# Extender-PCB.net
KiCad netlist of a schematic drawn in EAGLE
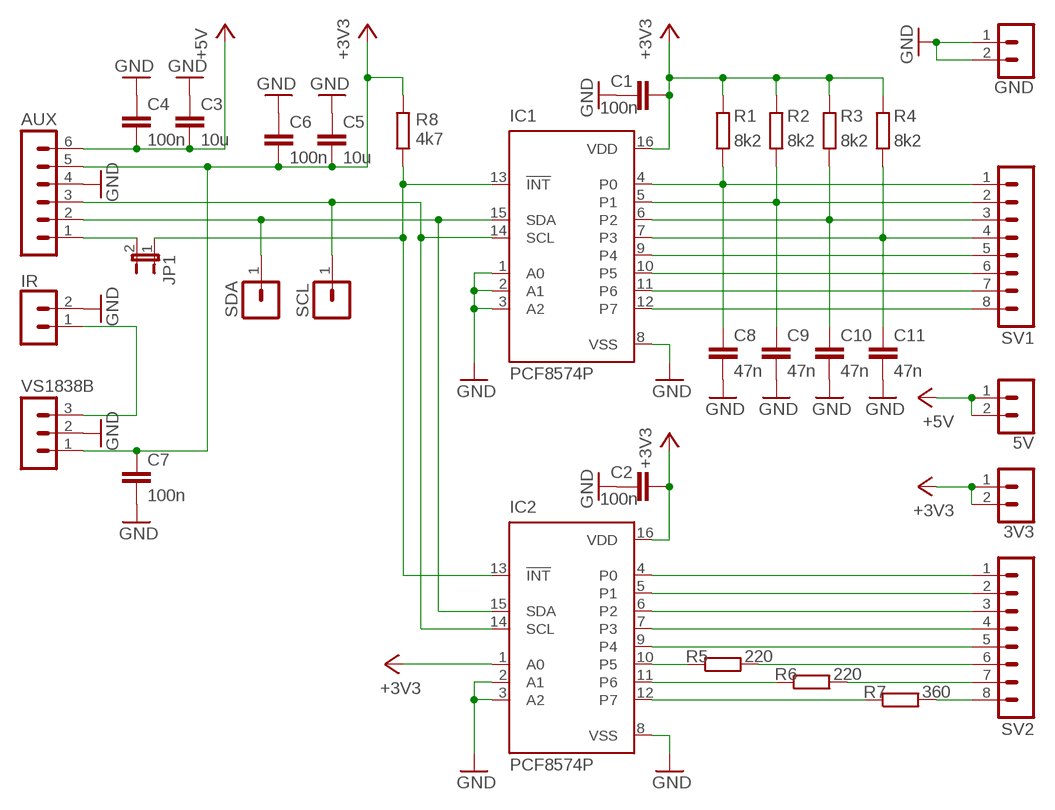
[diagram p0: schematic, sheet 1]

(export (version "E")
  (design (tool "Eeschema 10.0.6"))
  (components
    (comp (ref "3V3")
      (value "MA02-1")
      (footprint "eagle-import:MA02-1")
      (libsource (lib "eagle-import") (part "MA02-1"))
    )
    (comp (ref "5V")
      (value "MA02-1")
      (footprint "eagle-import:MA02-1")
      (libsource (lib "eagle-import") (part "MA02-1"))
    )
    (comp (ref "AUX")
      (value "MA06-1")
      (footprint "eagle-import:MA06-1")
      (libsource (lib "eagle-import") (part "MA06-1"))
    )
    (comp (ref "C1")
      (value "100n")
      (footprint "eagle-import:C1206")
      (libsource (lib "eagle-import") (part "C-EUC1206"))
    )
    (comp (ref "C2")
      (value "100n")
      (footprint "eagle-import:C1206")
      (libsource (lib "eagle-import") (part "C-EUC1206"))
    )
    (comp (ref "C3")
      (value "10u")
      (footprint "eagle-import:C1206")
      (libsource (lib "eagle-import") (part "C-EUC1206"))
    )
    (comp (ref "C4")
      (value "100n")
      (footprint "eagle-import:C1206")
      (libsource (lib "eagle-import") (part "C-EUC1206"))
    )
    (comp (ref "C5")
      (value "10u")
      (footprint "eagle-import:C1206")
      (libsource (lib "eagle-import") (part "C-EUC1206"))
    )
    (comp (ref "C6")
      (value "100n")
      (footprint "eagle-import:C1206")
      (libsource (lib "eagle-import") (part "C-EUC1206"))
    )
    (comp (ref "C7")
      (value "100n")
      (footprint "eagle-import:C1206")
      (libsource (lib "eagle-import") (part "C-EUC1206"))
    )
    (comp (ref "C8")
      (value "47n")
      (footprint "eagle-import:C1206")
      (libsource (lib "eagle-import") (part "C-EUC1206"))
    )
    (comp (ref "C9")
      (value "47n")
      (footprint "eagle-import:C1206")
      (libsource (lib "eagle-import") (part "C-EUC1206"))
    )
    (comp (ref "C10")
      (value "47n")
      (footprint "eagle-import:C1206")
      (libsource (lib "eagle-import") (part "C-EUC1206"))
    )
    (comp (ref "C11")
      (value "47n")
      (footprint "eagle-import:C1206")
      (libsource (lib "eagle-import") (part "C-EUC1206"))
    )
    (comp (ref "GND")
      (value "MA02-1")
      (footprint "eagle-import:MA02-1")
      (libsource (lib "eagle-import") (part "MA02-1"))
    )
    (comp (ref "IC1")
      (value "PCF8574P")
      (footprint "eagle-import:DIL16")
      (fields (field (name "MPN") "PCF8574PN"))
      (libsource (lib "eagle-import") (part "PCF8574P"))
    )
    (comp (ref "IC2")
      (value "PCF8574P")
      (footprint "eagle-import:DIL16")
      (fields (field (name "MPN") "PCF8574PN"))
      (libsource (lib "eagle-import") (part "PCF8574P"))
    )
    (comp (ref "IR")
      (value "MA02-1")
      (footprint "eagle-import:MA02-1")
      (libsource (lib "eagle-import") (part "MA02-1"))
    )
    (comp (ref "JP1")
      (value "JP1E")
      (footprint "eagle-import:JP1")
      (libsource (lib "eagle-import") (part "JP1E"))
    )
    (comp (ref "R1")
      (value "8k2")
      (footprint "eagle-import:R1206")
      (libsource (lib "eagle-import") (part "R-EU_R1206"))
    )
    (comp (ref "R2")
      (value "8k2")
      (footprint "eagle-import:R1206")
      (libsource (lib "eagle-import") (part "R-EU_R1206"))
    )
    (comp (ref "R3")
      (value "8k2")
      (footprint "eagle-import:R1206")
      (libsource (lib "eagle-import") (part "R-EU_R1206"))
    )
    (comp (ref "R4")
      (value "8k2")
      (footprint "eagle-import:R1206")
      (libsource (lib "eagle-import") (part "R-EU_R1206"))
    )
    (comp (ref "R5")
      (value "220")
      (footprint "eagle-import:0207_10")
      (libsource (lib "eagle-import") (part "R-EU_0207/10"))
    )
    (comp (ref "R6")
      (value "220")
      (footprint "eagle-import:0207_10")
      (libsource (lib "eagle-import") (part "R-EU_0207/10"))
    )
    (comp (ref "R7")
      (value "360")
      (footprint "eagle-import:0207_10")
      (libsource (lib "eagle-import") (part "R-EU_0207/10"))
    )
    (comp (ref "R8")
      (value "4k7")
      (footprint "eagle-import:0207_10")
      (libsource (lib "eagle-import") (part "R-EU_0207/10"))
    )
    (comp (ref "SCL")
      (value "MA01-1")
      (footprint "eagle-import:MA01-1")
      (libsource (lib "eagle-import") (part "MA01-1"))
    )
    (comp (ref "SDA")
      (value "MA01-1")
      (footprint "eagle-import:MA01-1")
      (libsource (lib "eagle-import") (part "MA01-1"))
    )
    (comp (ref "SV1")
      (value "MA08-1")
      (footprint "eagle-import:MA08-1")
      (libsource (lib "eagle-import") (part "MA08-1"))
    )
    (comp (ref "SV2")
      (value "MA08-1")
      (footprint "eagle-import:MA08-1")
      (libsource (lib "eagle-import") (part "MA08-1"))
    )
    (comp (ref "VS1838B")
      (value "MA03-1")
      (footprint "eagle-import:MA03-1")
      (libsource (lib "eagle-import") (part "MA03-1"))
    )
  )
  (nets
    (net (code "1") (name "+3V3") (class "Default")
      (node (ref "3V3") (pin "1") (pinfunction "1_1") (pintype "passive"))
      (node (ref "3V3") (pin "2") (pinfunction "2_2") (pintype "passive"))
      (node (ref "AUX") (pin "5") (pinfunction "5_5") (pintype "passive"))
      (node (ref "C1") (pin "2") (pinfunction "2_2") (pintype "passive"))
      (node (ref "C2") (pin "2") (pinfunction "2_2") (pintype "passive"))
      (node (ref "C5") (pin "2") (pinfunction "2_2") (pintype "passive"))
      (node (ref "C6") (pin "2") (pinfunction "2_2") (pintype "passive"))
      (node (ref "C7") (pin "1") (pinfunction "1_1") (pintype "passive"))
      (node (ref "IC1") (pin "16") (pinfunction "VDD_16") (pintype "power_in"))
      (node (ref "IC2") (pin "1") (pinfunction "A0_1") (pintype "input"))
      (node (ref "IC2") (pin "16") (pinfunction "VDD_16") (pintype "power_in"))
      (node (ref "R1") (pin "2") (pinfunction "2_2") (pintype "passive"))
      (node (ref "R2") (pin "2") (pinfunction "2_2") (pintype "passive"))
      (node (ref "R3") (pin "2") (pinfunction "2_2") (pintype "passive"))
      (node (ref "R4") (pin "2") (pinfunction "2_2") (pintype "passive"))
      (node (ref "R8") (pin "2") (pinfunction "2_2") (pintype "passive"))
      (node (ref "VS1838B") (pin "1") (pinfunction "1_1") (pintype "passive"))
    )
    (net (code "2") (name "+5V") (class "Default")
      (node (ref "5V") (pin "1") (pinfunction "1_1") (pintype "passive"))
      (node (ref "5V") (pin "2") (pinfunction "2_2") (pintype "passive"))
      (node (ref "AUX") (pin "6") (pinfunction "6_6") (pintype "passive"))
      (node (ref "C3") (pin "2") (pinfunction "2_2") (pintype "passive"))
      (node (ref "C4") (pin "2") (pinfunction "2_2") (pintype "passive"))
    )
    (net (code "3") (name "GND") (class "Default")
      (node (ref "AUX") (pin "4") (pinfunction "4_4") (pintype "passive"))
      (node (ref "C1") (pin "1") (pinfunction "1_1") (pintype "passive"))
      (node (ref "C10") (pin "2") (pinfunction "2_2") (pintype "passive"))
      (node (ref "C11") (pin "2") (pinfunction "2_2") (pintype "passive"))
      (node (ref "C2") (pin "1") (pinfunction "1_1") (pintype "passive"))
      (node (ref "C3") (pin "1") (pinfunction "1_1") (pintype "passive"))
      (node (ref "C4") (pin "1") (pinfunction "1_1") (pintype "passive"))
      (node (ref "C5") (pin "1") (pinfunction "1_1") (pintype "passive"))
      (node (ref "C6") (pin "1") (pinfunction "1_1") (pintype "passive"))
      (node (ref "C7") (pin "2") (pinfunction "2_2") (pintype "passive"))
      (node (ref "C8") (pin "2") (pinfunction "2_2") (pintype "passive"))
      (node (ref "C9") (pin "2") (pinfunction "2_2") (pintype "passive"))
      (node (ref "GND") (pin "1") (pinfunction "1_1") (pintype "passive"))
      (node (ref "GND") (pin "2") (pinfunction "2_2") (pintype "passive"))
      (node (ref "IC1") (pin "1") (pinfunction "A0_1") (pintype "input"))
      (node (ref "IC1") (pin "2") (pinfunction "A1_2") (pintype "input"))
      (node (ref "IC1") (pin "3") (pinfunction "A2_3") (pintype "input"))
      (node (ref "IC1") (pin "8") (pinfunction "VSS_8") (pintype "power_in"))
      (node (ref "IC2") (pin "2") (pinfunction "A1_2") (pintype "input"))
      (node (ref "IC2") (pin "3") (pinfunction "A2_3") (pintype "input"))
      (node (ref "IC2") (pin "8") (pinfunction "VSS_8") (pintype "power_in"))
      (node (ref "IR") (pin "2") (pinfunction "2_2") (pintype "passive"))
      (node (ref "VS1838B") (pin "2") (pinfunction "2_2") (pintype "passive"))
    )
    (net (code "4") (name "Net-(AUX-Pad1)") (class "Default")
      (node (ref "AUX") (pin "1") (pinfunction "1_1") (pintype "passive"))
      (node (ref "JP1") (pin "2") (pinfunction "2_2") (pintype "passive"))
    )
    (net (code "5") (name "Net-(IC1-P0)") (class "Default")
      (node (ref "C8") (pin "1") (pinfunction "1_1") (pintype "passive"))
      (node (ref "IC1") (pin "4") (pinfunction "P0_4") (pintype "bidirectional"))
      (node (ref "R1") (pin "1") (pinfunction "1_1") (pintype "passive"))
      (node (ref "SV1") (pin "1") (pinfunction "1_1") (pintype "passive"))
    )
    (net (code "6") (name "Net-(IC1-P1)") (class "Default")
      (node (ref "C9") (pin "1") (pinfunction "1_1") (pintype "passive"))
      (node (ref "IC1") (pin "5") (pinfunction "P1_5") (pintype "bidirectional"))
      (node (ref "R2") (pin "1") (pinfunction "1_1") (pintype "passive"))
      (node (ref "SV1") (pin "2") (pinfunction "2_2") (pintype "passive"))
    )
    (net (code "7") (name "Net-(IC1-P2)") (class "Default")
      (node (ref "C10") (pin "1") (pinfunction "1_1") (pintype "passive"))
      (node (ref "IC1") (pin "6") (pinfunction "P2_6") (pintype "bidirectional"))
      (node (ref "R3") (pin "1") (pinfunction "1_1") (pintype "passive"))
      (node (ref "SV1") (pin "3") (pinfunction "3_3") (pintype "passive"))
    )
    (net (code "8") (name "Net-(IC1-P3)") (class "Default")
      (node (ref "C11") (pin "1") (pinfunction "1_1") (pintype "passive"))
      (node (ref "IC1") (pin "7") (pinfunction "P3_7") (pintype "bidirectional"))
      (node (ref "R4") (pin "1") (pinfunction "1_1") (pintype "passive"))
      (node (ref "SV1") (pin "4") (pinfunction "4_4") (pintype "passive"))
    )
    (net (code "9") (name "Net-(IC1-P4)") (class "Default")
      (node (ref "IC1") (pin "9") (pinfunction "P4_9") (pintype "bidirectional"))
      (node (ref "SV1") (pin "5") (pinfunction "5_5") (pintype "passive"))
    )
    (net (code "10") (name "Net-(IC1-P5)") (class "Default")
      (node (ref "IC1") (pin "10") (pinfunction "P5_10") (pintype "bidirectional"))
      (node (ref "SV1") (pin "6") (pinfunction "6_6") (pintype "passive"))
    )
    (net (code "11") (name "Net-(IC1-P6)") (class "Default")
      (node (ref "IC1") (pin "11") (pinfunction "P6_11") (pintype "bidirectional"))
      (node (ref "SV1") (pin "7") (pinfunction "7_7") (pintype "passive"))
    )
    (net (code "12") (name "Net-(IC1-P7)") (class "Default")
      (node (ref "IC1") (pin "12") (pinfunction "P7_12") (pintype "bidirectional"))
      (node (ref "SV1") (pin "8") (pinfunction "8_8") (pintype "passive"))
    )
    (net (code "13") (name "Net-(IC1-SCL)") (class "Default")
      (node (ref "AUX") (pin "3") (pinfunction "3_3") (pintype "passive"))
      (node (ref "IC1") (pin "14") (pinfunction "SCL_14") (pintype "input"))
      (node (ref "IC2") (pin "14") (pinfunction "SCL_14") (pintype "input"))
      (node (ref "SCL") (pin "1") (pinfunction "1_1") (pintype "passive"))
    )
    (net (code "14") (name "Net-(IC1-SDA)") (class "Default")
      (node (ref "AUX") (pin "2") (pinfunction "2_2") (pintype "passive"))
      (node (ref "IC1") (pin "15") (pinfunction "SDA_15") (pintype "bidirectional"))
      (node (ref "IC2") (pin "15") (pinfunction "SDA_15") (pintype "bidirectional"))
      (node (ref "SDA") (pin "1") (pinfunction "1_1") (pintype "passive"))
    )
    (net (code "15") (name "Net-(IC1-~{INT})") (class "Default")
      (node (ref "IC1") (pin "13") (pinfunction "~{INT}_13") (pintype "output"))
      (node (ref "IC2") (pin "13") (pinfunction "~{INT}_13") (pintype "output"))
      (node (ref "JP1") (pin "1") (pinfunction "1_1") (pintype "passive"))
      (node (ref "R8") (pin "1") (pinfunction "1_1") (pintype "passive"))
    )
    (net (code "16") (name "Net-(IC2-P0)") (class "Default")
      (node (ref "IC2") (pin "4") (pinfunction "P0_4") (pintype "bidirectional"))
      (node (ref "SV2") (pin "1") (pinfunction "1_1") (pintype "passive"))
    )
    (net (code "17") (name "Net-(IC2-P1)") (class "Default")
      (node (ref "IC2") (pin "5") (pinfunction "P1_5") (pintype "bidirectional"))
      (node (ref "SV2") (pin "2") (pinfunction "2_2") (pintype "passive"))
    )
    (net (code "18") (name "Net-(IC2-P2)") (class "Default")
      (node (ref "IC2") (pin "6") (pinfunction "P2_6") (pintype "bidirectional"))
      (node (ref "SV2") (pin "3") (pinfunction "3_3") (pintype "passive"))
    )
    (net (code "19") (name "Net-(IC2-P3)") (class "Default")
      (node (ref "IC2") (pin "7") (pinfunction "P3_7") (pintype "bidirectional"))
      (node (ref "SV2") (pin "4") (pinfunction "4_4") (pintype "passive"))
    )
    (net (code "20") (name "Net-(IC2-P4)") (class "Default")
      (node (ref "IC2") (pin "9") (pinfunction "P4_9") (pintype "bidirectional"))
      (node (ref "SV2") (pin "5") (pinfunction "5_5") (pintype "passive"))
    )
    (net (code "21") (name "Net-(IC2-P5)") (class "Default")
      (node (ref "IC2") (pin "10") (pinfunction "P5_10") (pintype "bidirectional"))
      (node (ref "R5") (pin "1") (pinfunction "1_1") (pintype "passive"))
    )
    (net (code "22") (name "Net-(IC2-P6)") (class "Default")
      (node (ref "IC2") (pin "11") (pinfunction "P6_11") (pintype "bidirectional"))
      (node (ref "R6") (pin "1") (pinfunction "1_1") (pintype "passive"))
    )
    (net (code "23") (name "Net-(IC2-P7)") (class "Default")
      (node (ref "IC2") (pin "12") (pinfunction "P7_12") (pintype "bidirectional"))
      (node (ref "R7") (pin "1") (pinfunction "1_1") (pintype "passive"))
    )
    (net (code "24") (name "Net-(IR-Pad1)") (class "Default")
      (node (ref "IR") (pin "1") (pinfunction "1_1") (pintype "passive"))
      (node (ref "VS1838B") (pin "3") (pinfunction "3_3") (pintype "passive"))
    )
    (net (code "25") (name "Net-(R5-Pad2)") (class "Default")
      (node (ref "R5") (pin "2") (pinfunction "2_2") (pintype "passive"))
      (node (ref "SV2") (pin "6") (pinfunction "6_6") (pintype "passive"))
    )
    (net (code "26") (name "Net-(R6-Pad2)") (class "Default")
      (node (ref "R6") (pin "2") (pinfunction "2_2") (pintype "passive"))
      (node (ref "SV2") (pin "7") (pinfunction "7_7") (pintype "passive"))
    )
    (net (code "27") (name "Net-(R7-Pad2)") (class "Default")
      (node (ref "R7") (pin "2") (pinfunction "2_2") (pintype "passive"))
      (node (ref "SV2") (pin "8") (pinfunction "8_8") (pintype "passive"))
    )
  )
)
